# untitled.net
KiCad netlist of a schematic drawn in EAGLE
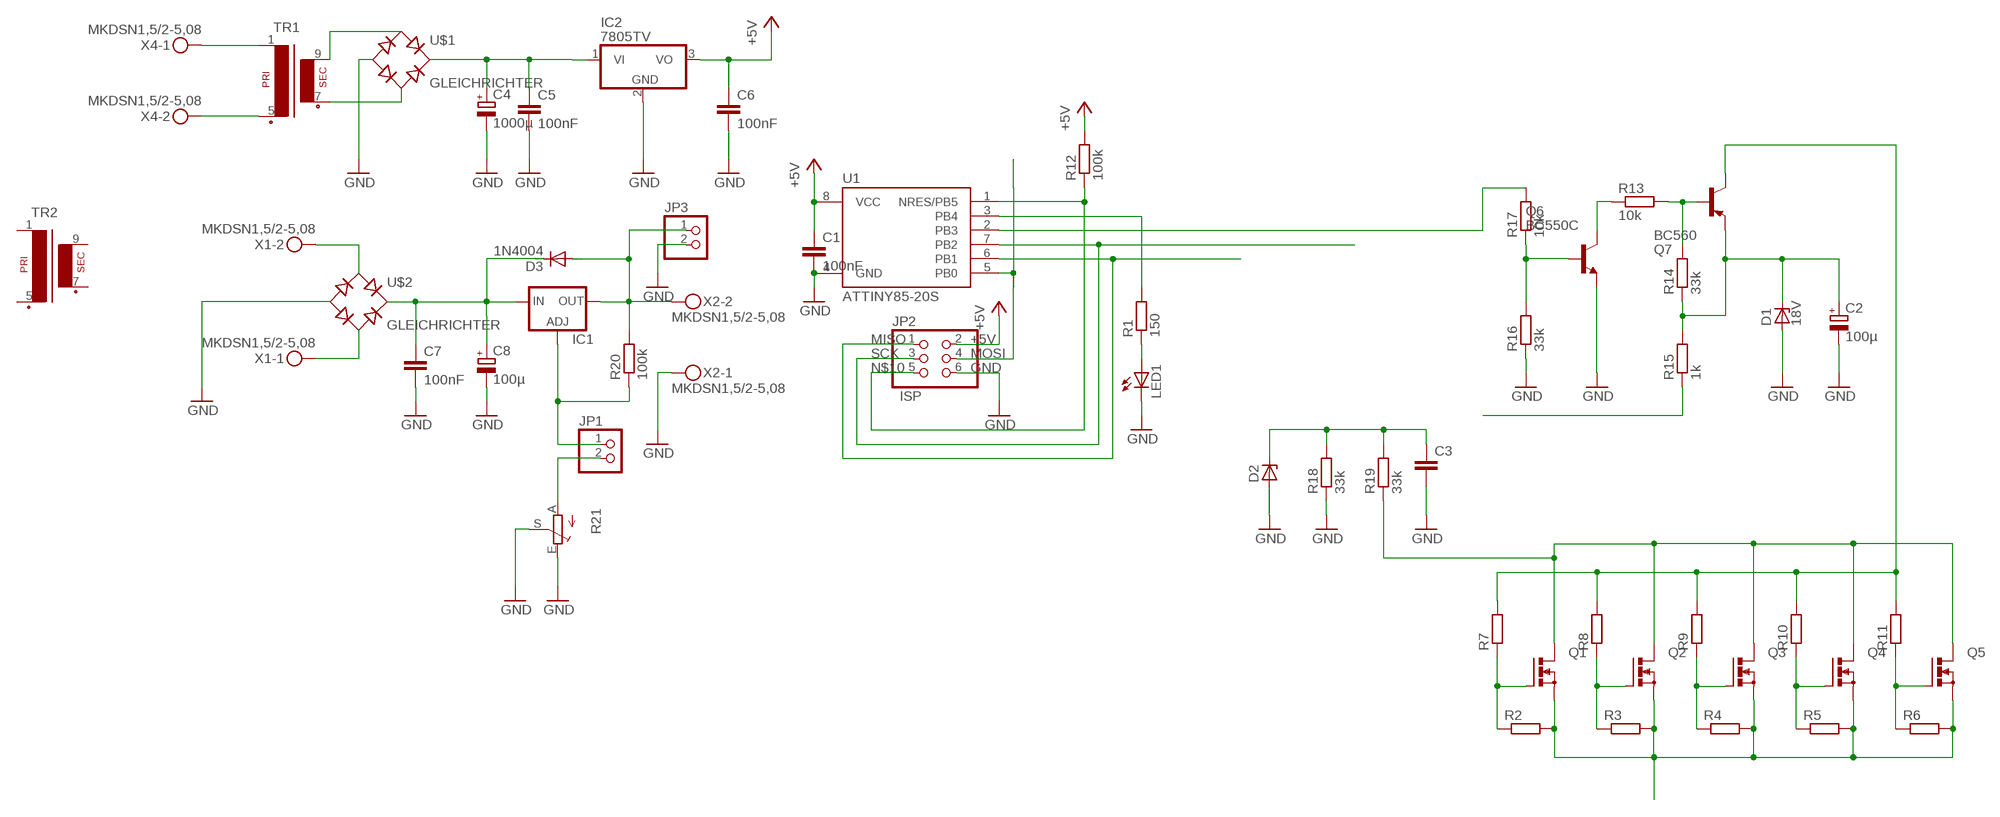
[diagram p0: schematic, sheet 1]

(export (version "E")
  (design (tool "Eeschema 10.0.6"))
  (components
    (comp (ref "C1")
      (value "100nF")
      (footprint "eagle-import:C0805")
      (libsource (lib "eagle-import") (part "C-EUC0805"))
    )
    (comp (ref "C2")
      (value "100µ")
      (footprint "eagle-import:E2,5-7")
      (libsource (lib "eagle-import") (part "resistor_CPOL-EUE2.5-7"))
    )
    (comp (ref "C3")
      (value "C-EUC0603K")
      (footprint "eagle-import:C0603K")
      (libsource (lib "eagle-import") (part "C-EUC0603K"))
    )
    (comp (ref "C4")
      (value "1000µ")
      (footprint "eagle-import:E3,5-8")
      (libsource (lib "eagle-import") (part "CPOL-EUE3.5-8"))
    )
    (comp (ref "C5")
      (value "100nF")
      (footprint "eagle-import:C0805")
      (libsource (lib "eagle-import") (part "C-EUC0805"))
    )
    (comp (ref "C6")
      (value "100nF")
      (footprint "eagle-import:C0805")
      (libsource (lib "eagle-import") (part "C-EUC0805"))
    )
    (comp (ref "C7")
      (value "100nF")
      (footprint "eagle-import:C0805")
      (libsource (lib "eagle-import") (part "C-EUC0805"))
    )
    (comp (ref "C8")
      (value "100µ")
      (footprint "eagle-import:E3,5-8")
      (libsource (lib "eagle-import") (part "CPOL-EUE3.5-8"))
    )
    (comp (ref "D1")
      (value "18V")
      (footprint "eagle-import:SOD80C")
      (libsource (lib "eagle-import") (part "ZENER-DIODESOD80C"))
    )
    (comp (ref "D2")
      (value "ZENER-DIODESOT23")
      (footprint "eagle-import:SOT23")
      (libsource (lib "eagle-import") (part "ZENER-DIODESOT23"))
    )
    (comp (ref "D3")
      (value "1N4004")
      (footprint "eagle-import:DO41-10")
      (libsource (lib "eagle-import") (part "1N4004"))
    )
    (comp (ref "IC1")
      (value "LM317TS")
      (footprint "eagle-import:317TS")
      (libsource (lib "eagle-import") (part "LM317TS"))
    )
    (comp (ref "IC2")
      (value "7805TV")
      (footprint "eagle-import:TO220V")
      (libsource (lib "eagle-import") (part "78TV05"))
    )
    (comp (ref "JP1")
      (value "PINHD-1X2")
      (footprint "eagle-import:1X02")
      (libsource (lib "eagle-import") (part "PINHD-1X2"))
    )
    (comp (ref "JP2")
      (value "PINHD-2X3")
      (footprint "eagle-import:2X03")
      (libsource (lib "eagle-import") (part "PINHD-2X3"))
    )
    (comp (ref "JP3")
      (value "PINHD-1X2")
      (footprint "eagle-import:1X02")
      (libsource (lib "eagle-import") (part "PINHD-1X2"))
    )
    (comp (ref "LED1")
      (value "LED3MM")
      (footprint "eagle-import:LED3MM")
      (libsource (lib "eagle-import") (part "LED3MM"))
    )
    (comp (ref "Q1")
      (value "PMOSFET_NTO220BV")
      (footprint "eagle-import:TO220BV")
      (libsource (lib "eagle-import") (part "PMOSFET_NTO220BV"))
    )
    (comp (ref "Q2")
      (value "PMOSFET_NTO220BV")
      (footprint "eagle-import:TO220BV")
      (libsource (lib "eagle-import") (part "PMOSFET_NTO220BV"))
    )
    (comp (ref "Q3")
      (value "PMOSFET_NTO220BV")
      (footprint "eagle-import:TO220BV")
      (libsource (lib "eagle-import") (part "PMOSFET_NTO220BV"))
    )
    (comp (ref "Q4")
      (value "PMOSFET_NTO220BV")
      (footprint "eagle-import:TO220BV")
      (libsource (lib "eagle-import") (part "PMOSFET_NTO220BV"))
    )
    (comp (ref "Q5")
      (value "PMOSFET_NTO220BV")
      (footprint "eagle-import:TO220BV")
      (libsource (lib "eagle-import") (part "PMOSFET_NTO220BV"))
    )
    (comp (ref "Q6")
      (value "BC550C")
      (footprint "eagle-import:TO92-EBC")
      (libsource (lib "eagle-import") (part "BC550C"))
    )
    (comp (ref "Q7")
      (value "BC560")
      (footprint "eagle-import:TO92-EBC")
      (libsource (lib "eagle-import") (part "BC560"))
    )
    (comp (ref "R1")
      (value "150")
      (footprint "eagle-import:R1206")
      (libsource (lib "eagle-import") (part "R-EU_R1206"))
    )
    (comp (ref "R2")
      (value "R-EU_0207/10")
      (footprint "eagle-import:0207_10")
      (libsource (lib "eagle-import") (part "resistor_R-EU_0207/10"))
    )
    (comp (ref "R3")
      (value "R-EU_0207/10")
      (footprint "eagle-import:0207_10")
      (libsource (lib "eagle-import") (part "resistor_R-EU_0207/10"))
    )
    (comp (ref "R4")
      (value "R-EU_0207/10")
      (footprint "eagle-import:0207_10")
      (libsource (lib "eagle-import") (part "resistor_R-EU_0207/10"))
    )
    (comp (ref "R5")
      (value "R-EU_0207/10")
      (footprint "eagle-import:0207_10")
      (libsource (lib "eagle-import") (part "resistor_R-EU_0207/10"))
    )
    (comp (ref "R6")
      (value "R-EU_0207/10")
      (footprint "eagle-import:0207_10")
      (libsource (lib "eagle-import") (part "resistor_R-EU_0207/10"))
    )
    (comp (ref "R7")
      (value "R-EU_0207/10")
      (footprint "eagle-import:0207_10")
      (libsource (lib "eagle-import") (part "resistor_R-EU_0207/10"))
    )
    (comp (ref "R8")
      (value "R-EU_0207/10")
      (footprint "eagle-import:0207_10")
      (libsource (lib "eagle-import") (part "resistor_R-EU_0207/10"))
    )
    (comp (ref "R9")
      (value "R-EU_0207/10")
      (footprint "eagle-import:0207_10")
      (libsource (lib "eagle-import") (part "resistor_R-EU_0207/10"))
    )
    (comp (ref "R10")
      (value "R-EU_0207/10")
      (footprint "eagle-import:0207_10")
      (libsource (lib "eagle-import") (part "resistor_R-EU_0207/10"))
    )
    (comp (ref "R11")
      (value "R-EU_0207/10")
      (footprint "eagle-import:0207_10")
      (libsource (lib "eagle-import") (part "resistor_R-EU_0207/10"))
    )
    (comp (ref "R12")
      (value "100k")
      (footprint "eagle-import:R1206")
      (libsource (lib "eagle-import") (part "R-EU_R1206"))
    )
    (comp (ref "R13")
      (value "10k")
      (footprint "eagle-import:R1206")
      (libsource (lib "eagle-import") (part "resistor_R-EU_R1206"))
    )
    (comp (ref "R14")
      (value "33k")
      (footprint "eagle-import:R1206")
      (libsource (lib "eagle-import") (part "resistor_R-EU_R1206"))
    )
    (comp (ref "R15")
      (value "1k")
      (footprint "eagle-import:R1206")
      (libsource (lib "eagle-import") (part "resistor_R-EU_R1206"))
    )
    (comp (ref "R16")
      (value "33k")
      (footprint "eagle-import:R1206")
      (libsource (lib "eagle-import") (part "resistor_R-EU_R1206"))
    )
    (comp (ref "R17")
      (value "10k")
      (footprint "eagle-import:R1206")
      (libsource (lib "eagle-import") (part "resistor_R-EU_R1206"))
    )
    (comp (ref "R18")
      (value "33k")
      (footprint "eagle-import:R1206")
      (libsource (lib "eagle-import") (part "resistor_R-EU_R1206"))
    )
    (comp (ref "R19")
      (value "33k")
      (footprint "eagle-import:R1206")
      (libsource (lib "eagle-import") (part "resistor_R-EU_R1206"))
    )
    (comp (ref "R20")
      (value "100k")
      (footprint "eagle-import:R1206")
      (libsource (lib "eagle-import") (part "R-EU_R1206"))
    )
    (comp (ref "R21")
      (value "TRIM_EU-PT10")
      (footprint "eagle-import:PT-10")
      (libsource (lib "eagle-import") (part "TRIM_EU-PT10"))
    )
    (comp (ref "TR1")
      (value "EI38-1")
      (footprint "eagle-import:EI38-1")
      (libsource (lib "eagle-import") (part "EI38-1"))
    )
    (comp (ref "TR2")
      (value "EI38-1")
      (footprint "eagle-import:EI38-1")
      (libsource (lib "eagle-import") (part "EI38-1"))
    )
    (comp (ref "U$1")
      (value "GLEICHRICHTER")
      (footprint "eagle-import:KBPC1")
      (libsource (lib "eagle-import") (part "GLEICHRICHTER"))
    )
    (comp (ref "U$2")
      (value "GLEICHRICHTER")
      (footprint "eagle-import:KBPC1")
      (libsource (lib "eagle-import") (part "GLEICHRICHTER"))
    )
    (comp (ref "U1")
      (value "ATTINY85-20S")
      (footprint "eagle-import:SOIC8_EIAJ_208MIL")
      (libsource (lib "eagle-import") (part "ATTINY85S-20"))
    )
    (comp (ref "X1")
      (value "MKDSN1,5/2-5,08")
      (footprint "eagle-import:MKDSN1,5_2-5,08")
      (libsource (lib "eagle-import") (part "MKDSN1,5/2-5,08"))
    )
    (comp (ref "X2")
      (value "MKDSN1,5/2-5,08")
      (footprint "eagle-import:MKDSN1,5_2-5,08")
      (libsource (lib "eagle-import") (part "MKDSN1,5/2-5,08"))
    )
    (comp (ref "X4")
      (value "MKDSN1,5/2-5,08")
      (footprint "eagle-import:MKDSN1,5_2-5,08")
      (libsource (lib "eagle-import") (part "MKDSN1,5/2-5,08"))
    )
  )
  (nets
    (net (code "1") (name "+5V") (class "Default")
      (node (ref "C1") (pin "1") (pinfunction "1_1") (pintype "passive"))
      (node (ref "C6") (pin "1") (pinfunction "1_1") (pintype "passive"))
      (node (ref "IC2") (pin "3") (pinfunction "VO_3") (pintype "passive"))
      (node (ref "JP2") (pin "2") (pinfunction "2_2") (pintype "passive"))
      (node (ref "R12") (pin "2") (pinfunction "2_2") (pintype "passive"))
      (node (ref "U1") (pin "8") (pinfunction "VCC_8") (pintype "power_in"))
    )
    (net (code "2") (name "/MISO") (class "Default")
      (node (ref "JP2") (pin "1") (pinfunction "1_1") (pintype "passive"))
      (node (ref "U1") (pin "6") (pinfunction "PB1_6") (pintype "bidirectional"))
    )
    (net (code "3") (name "/MOSI") (class "Default")
      (node (ref "JP2") (pin "4") (pinfunction "4_4") (pintype "passive"))
      (node (ref "U1") (pin "5") (pinfunction "PB0_5") (pintype "bidirectional"))
    )
    (net (code "4") (name "/N$10") (class "Default")
      (node (ref "JP2") (pin "5") (pinfunction "5_5") (pintype "passive"))
      (node (ref "R12") (pin "1") (pinfunction "1_1") (pintype "passive"))
      (node (ref "U1") (pin "1") (pinfunction "NRES/PB5_1") (pintype "bidirectional"))
    )
    (net (code "5") (name "/SCK") (class "Default")
      (node (ref "JP2") (pin "3") (pinfunction "3_3") (pintype "passive"))
      (node (ref "U1") (pin "7") (pinfunction "PB2_7") (pintype "bidirectional"))
    )
    (net (code "6") (name "GND") (class "Default")
      (node (ref "C1") (pin "2") (pinfunction "2_2") (pintype "passive"))
      (node (ref "C2") (pin "-") (pinfunction "-_-") (pintype "passive"))
      (node (ref "C3") (pin "2") (pinfunction "2_2") (pintype "passive"))
      (node (ref "C4") (pin "-") (pinfunction "-_-") (pintype "passive"))
      (node (ref "C5") (pin "2") (pinfunction "2_2") (pintype "passive"))
      (node (ref "C6") (pin "2") (pinfunction "2_2") (pintype "passive"))
      (node (ref "C7") (pin "2") (pinfunction "2_2") (pintype "passive"))
      (node (ref "C8") (pin "-") (pinfunction "-_-") (pintype "passive"))
      (node (ref "D1") (pin "A") (pinfunction "A_A") (pintype "passive"))
      (node (ref "D2") (pin "1") (pinfunction "A_1") (pintype "passive"))
      (node (ref "IC2") (pin "2") (pinfunction "GND_2") (pintype "passive"))
      (node (ref "JP2") (pin "6") (pinfunction "6_6") (pintype "passive"))
      (node (ref "JP3") (pin "2") (pinfunction "2_2") (pintype "passive"))
      (node (ref "LED1") (pin "K") (pinfunction "C_K") (pintype "passive"))
      (node (ref "Q6") (pin "E") (pinfunction "E_E") (pintype "passive"))
      (node (ref "R16") (pin "1") (pinfunction "1_1") (pintype "passive"))
      (node (ref "R18") (pin "1") (pinfunction "1_1") (pintype "passive"))
      (node (ref "R21") (pin "E") (pinfunction "E_E") (pintype "passive"))
      (node (ref "R21") (pin "S") (pinfunction "S_S") (pintype "passive"))
      (node (ref "U$1") (pin "-") (pinfunction "-_-") (pintype "passive"))
      (node (ref "U$2") (pin "-") (pinfunction "-_-") (pintype "passive"))
      (node (ref "U1") (pin "4") (pinfunction "GND_4") (pintype "power_in"))
      (node (ref "X2") (pin "1") (pinfunction "KL_1") (pintype "passive"))
    )
    (net (code "7") (name "Net-(C2-Pad+)") (class "Default")
      (node (ref "C2") (pin "+") (pinfunction "+_+") (pintype "passive"))
      (node (ref "D1") (pin "C") (pinfunction "C_C") (pintype "passive"))
      (node (ref "Q7") (pin "E") (pinfunction "E_E") (pintype "passive"))
      (node (ref "R14") (pin "1") (pinfunction "1_1") (pintype "passive"))
      (node (ref "R15") (pin "2") (pinfunction "2_2") (pintype "passive"))
    )
    (net (code "8") (name "Net-(D2-C)") (class "Default")
      (node (ref "C3") (pin "1") (pinfunction "1_1") (pintype "passive"))
      (node (ref "D2") (pin "3") (pinfunction "C_3") (pintype "passive"))
      (node (ref "R18") (pin "2") (pinfunction "2_2") (pintype "passive"))
      (node (ref "R19") (pin "2") (pinfunction "2_2") (pintype "passive"))
    )
    (net (code "9") (name "Net-(IC1-ADJ)") (class "Default")
      (node (ref "IC1") (pin "1") (pinfunction "ADJ_1") (pintype "input"))
      (node (ref "JP1") (pin "1") (pinfunction "1_1") (pintype "passive"))
      (node (ref "R20") (pin "1") (pinfunction "1_1") (pintype "passive"))
    )
    (net (code "10") (name "Net-(IC1-IN)") (class "Default")
      (node (ref "C7") (pin "1") (pinfunction "1_1") (pintype "passive"))
      (node (ref "C8") (pin "+") (pinfunction "+_+") (pintype "passive"))
      (node (ref "D3") (pin "C") (pinfunction "C_C") (pintype "passive"))
      (node (ref "IC1") (pin "3") (pinfunction "IN_3") (pintype "input"))
      (node (ref "U$2") (pin "+") (pinfunction "+_+") (pintype "passive"))
    )
    (net (code "11") (name "Net-(IC1-OUT)") (class "Default")
      (node (ref "D3") (pin "A") (pinfunction "A_A") (pintype "passive"))
      (node (ref "IC1") (pin "2") (pinfunction "OUT_2") (pintype "passive"))
      (node (ref "JP3") (pin "1") (pinfunction "1_1") (pintype "passive"))
      (node (ref "R20") (pin "2") (pinfunction "2_2") (pintype "passive"))
      (node (ref "X2") (pin "2") (pinfunction "KL_2") (pintype "passive"))
    )
    (net (code "12") (name "Net-(IC2-VI)") (class "Default")
      (node (ref "C4") (pin "+") (pinfunction "+_+") (pintype "passive"))
      (node (ref "C5") (pin "1") (pinfunction "1_1") (pintype "passive"))
      (node (ref "IC2") (pin "1") (pinfunction "VI_1") (pintype "input"))
      (node (ref "U$1") (pin "+") (pinfunction "+_+") (pintype "passive"))
    )
    (net (code "13") (name "Net-(JP1-Pad2)") (class "Default")
      (node (ref "JP1") (pin "2") (pinfunction "2_2") (pintype "passive"))
      (node (ref "R21") (pin "A") (pinfunction "A_A") (pintype "passive"))
    )
    (net (code "14") (name "Net-(LED1-PadA)") (class "Default")
      (node (ref "LED1") (pin "A") (pinfunction "A_A") (pintype "passive"))
      (node (ref "R1") (pin "1") (pinfunction "1_1") (pintype "passive"))
    )
    (net (code "15") (name "Net-(Q1-PadD)") (class "Default")
      (node (ref "Q1") (pin "D") (pinfunction "D_D") (pintype "passive"))
      (node (ref "Q2") (pin "D") (pinfunction "D_D") (pintype "passive"))
      (node (ref "Q3") (pin "D") (pinfunction "D_D") (pintype "passive"))
      (node (ref "Q4") (pin "D") (pinfunction "D_D") (pintype "passive"))
      (node (ref "Q5") (pin "D") (pinfunction "D_D") (pintype "passive"))
      (node (ref "R19") (pin "1") (pinfunction "1_1") (pintype "passive"))
    )
    (net (code "16") (name "Net-(Q1-PadG)") (class "Default")
      (node (ref "Q1") (pin "G") (pinfunction "G_G") (pintype "passive"))
      (node (ref "R2") (pin "1") (pinfunction "1_1") (pintype "passive"))
      (node (ref "R7") (pin "1") (pinfunction "1_1") (pintype "passive"))
    )
    (net (code "17") (name "Net-(Q1-PadS)") (class "Default")
      (node (ref "Q1") (pin "S") (pinfunction "S_S") (pintype "passive"))
      (node (ref "Q2") (pin "S") (pinfunction "S_S") (pintype "passive"))
      (node (ref "Q3") (pin "S") (pinfunction "S_S") (pintype "passive"))
      (node (ref "Q4") (pin "S") (pinfunction "S_S") (pintype "passive"))
      (node (ref "Q5") (pin "S") (pinfunction "S_S") (pintype "passive"))
      (node (ref "R2") (pin "2") (pinfunction "2_2") (pintype "passive"))
      (node (ref "R3") (pin "2") (pinfunction "2_2") (pintype "passive"))
      (node (ref "R4") (pin "2") (pinfunction "2_2") (pintype "passive"))
      (node (ref "R5") (pin "2") (pinfunction "2_2") (pintype "passive"))
      (node (ref "R6") (pin "2") (pinfunction "2_2") (pintype "passive"))
    )
    (net (code "18") (name "Net-(Q2-PadG)") (class "Default")
      (node (ref "Q2") (pin "G") (pinfunction "G_G") (pintype "passive"))
      (node (ref "R3") (pin "1") (pinfunction "1_1") (pintype "passive"))
      (node (ref "R8") (pin "1") (pinfunction "1_1") (pintype "passive"))
    )
    (net (code "19") (name "Net-(Q3-PadG)") (class "Default")
      (node (ref "Q3") (pin "G") (pinfunction "G_G") (pintype "passive"))
      (node (ref "R4") (pin "1") (pinfunction "1_1") (pintype "passive"))
      (node (ref "R9") (pin "1") (pinfunction "1_1") (pintype "passive"))
    )
    (net (code "20") (name "Net-(Q4-PadG)") (class "Default")
      (node (ref "Q4") (pin "G") (pinfunction "G_G") (pintype "passive"))
      (node (ref "R10") (pin "1") (pinfunction "1_1") (pintype "passive"))
      (node (ref "R5") (pin "1") (pinfunction "1_1") (pintype "passive"))
    )
    (net (code "21") (name "Net-(Q5-PadG)") (class "Default")
      (node (ref "Q5") (pin "G") (pinfunction "G_G") (pintype "passive"))
      (node (ref "R11") (pin "1") (pinfunction "1_1") (pintype "passive"))
      (node (ref "R6") (pin "1") (pinfunction "1_1") (pintype "passive"))
    )
    (net (code "22") (name "Net-(Q6-PadB)") (class "Default")
      (node (ref "Q6") (pin "B") (pinfunction "B_B") (pintype "passive"))
      (node (ref "R16") (pin "2") (pinfunction "2_2") (pintype "passive"))
      (node (ref "R17") (pin "1") (pinfunction "1_1") (pintype "passive"))
    )
    (net (code "23") (name "Net-(Q6-PadC)") (class "Default")
      (node (ref "Q6") (pin "C") (pinfunction "C_C") (pintype "passive"))
      (node (ref "R13") (pin "1") (pinfunction "1_1") (pintype "passive"))
    )
    (net (code "24") (name "Net-(Q7-PadB)") (class "Default")
      (node (ref "Q7") (pin "B") (pinfunction "B_B") (pintype "passive"))
      (node (ref "R13") (pin "2") (pinfunction "2_2") (pintype "passive"))
      (node (ref "R14") (pin "2") (pinfunction "2_2") (pintype "passive"))
    )
    (net (code "25") (name "Net-(Q7-PadC)") (class "Default")
      (node (ref "Q7") (pin "C") (pinfunction "C_C") (pintype "passive"))
      (node (ref "R10") (pin "2") (pinfunction "2_2") (pintype "passive"))
      (node (ref "R11") (pin "2") (pinfunction "2_2") (pintype "passive"))
      (node (ref "R7") (pin "2") (pinfunction "2_2") (pintype "passive"))
      (node (ref "R8") (pin "2") (pinfunction "2_2") (pintype "passive"))
      (node (ref "R9") (pin "2") (pinfunction "2_2") (pintype "passive"))
    )
    (net (code "26") (name "Net-(TR1-P1)") (class "Default")
      (node (ref "TR1") (pin "1") (pinfunction "P1_1") (pintype "passive"))
      (node (ref "X4") (pin "1") (pinfunction "KL_1") (pintype "passive"))
    )
    (net (code "27") (name "Net-(TR1-P2)") (class "Default")
      (node (ref "TR1") (pin "5") (pinfunction "P2_5") (pintype "passive"))
      (node (ref "X4") (pin "2") (pinfunction "KL_2") (pintype "passive"))
    )
    (net (code "28") (name "Net-(TR1-S3)") (class "Default")
      (node (ref "TR1") (pin "7") (pinfunction "S3_7") (pintype "passive"))
      (node (ref "U$1") (pin "AC2") (pinfunction "AC2_AC2") (pintype "passive"))
    )
    (net (code "29") (name "Net-(TR1-S4)") (class "Default")
      (node (ref "TR1") (pin "9") (pinfunction "S4_9") (pintype "passive"))
      (node (ref "U$1") (pin "AC1") (pinfunction "AC1_AC1") (pintype "passive"))
    )
    (net (code "30") (name "Net-(U1-PB3)") (class "Default")
      (node (ref "R17") (pin "2") (pinfunction "2_2") (pintype "passive"))
      (node (ref "U1") (pin "2") (pinfunction "PB3_2") (pintype "bidirectional"))
    )
    (net (code "31") (name "Net-(U1-PB4)") (class "Default")
      (node (ref "R1") (pin "2") (pinfunction "2_2") (pintype "passive"))
      (node (ref "U1") (pin "3") (pinfunction "PB4_3") (pintype "bidirectional"))
    )
    (net (code "32") (name "Net-(X1A-KL)") (class "Default")
      (node (ref "U$2") (pin "AC2") (pinfunction "AC2_AC2") (pintype "passive"))
      (node (ref "X1") (pin "1") (pinfunction "KL_1") (pintype "passive"))
    )
    (net (code "33") (name "Net-(X1B-KL)") (class "Default")
      (node (ref "U$2") (pin "AC1") (pinfunction "AC1_AC1") (pintype "passive"))
      (node (ref "X1") (pin "2") (pinfunction "KL_2") (pintype "passive"))
    )
    (net (code "34") (name "unconnected-(R15-Pad1)") (class "Default")
      (node (ref "R15") (pin "1") (pinfunction "1_1") (pintype "passive"))
    )
    (net (code "35") (name "unconnected-(TR2-P1-Pad1)") (class "Default")
      (node (ref "TR2") (pin "1") (pinfunction "P1_1") (pintype "passive"))
    )
    (net (code "36") (name "unconnected-(TR2-P2-Pad5)") (class "Default")
      (node (ref "TR2") (pin "5") (pinfunction "P2_5") (pintype "passive"))
    )
    (net (code "37") (name "unconnected-(TR2-S3-Pad7)") (class "Default")
      (node (ref "TR2") (pin "7") (pinfunction "S3_7") (pintype "passive"))
    )
    (net (code "38") (name "unconnected-(TR2-S4-Pad9)") (class "Default")
      (node (ref "TR2") (pin "9") (pinfunction "S4_9") (pintype "passive"))
    )
  )
)
